# hall.net
KiCad netlist of a schematic drawn in Altium Designer
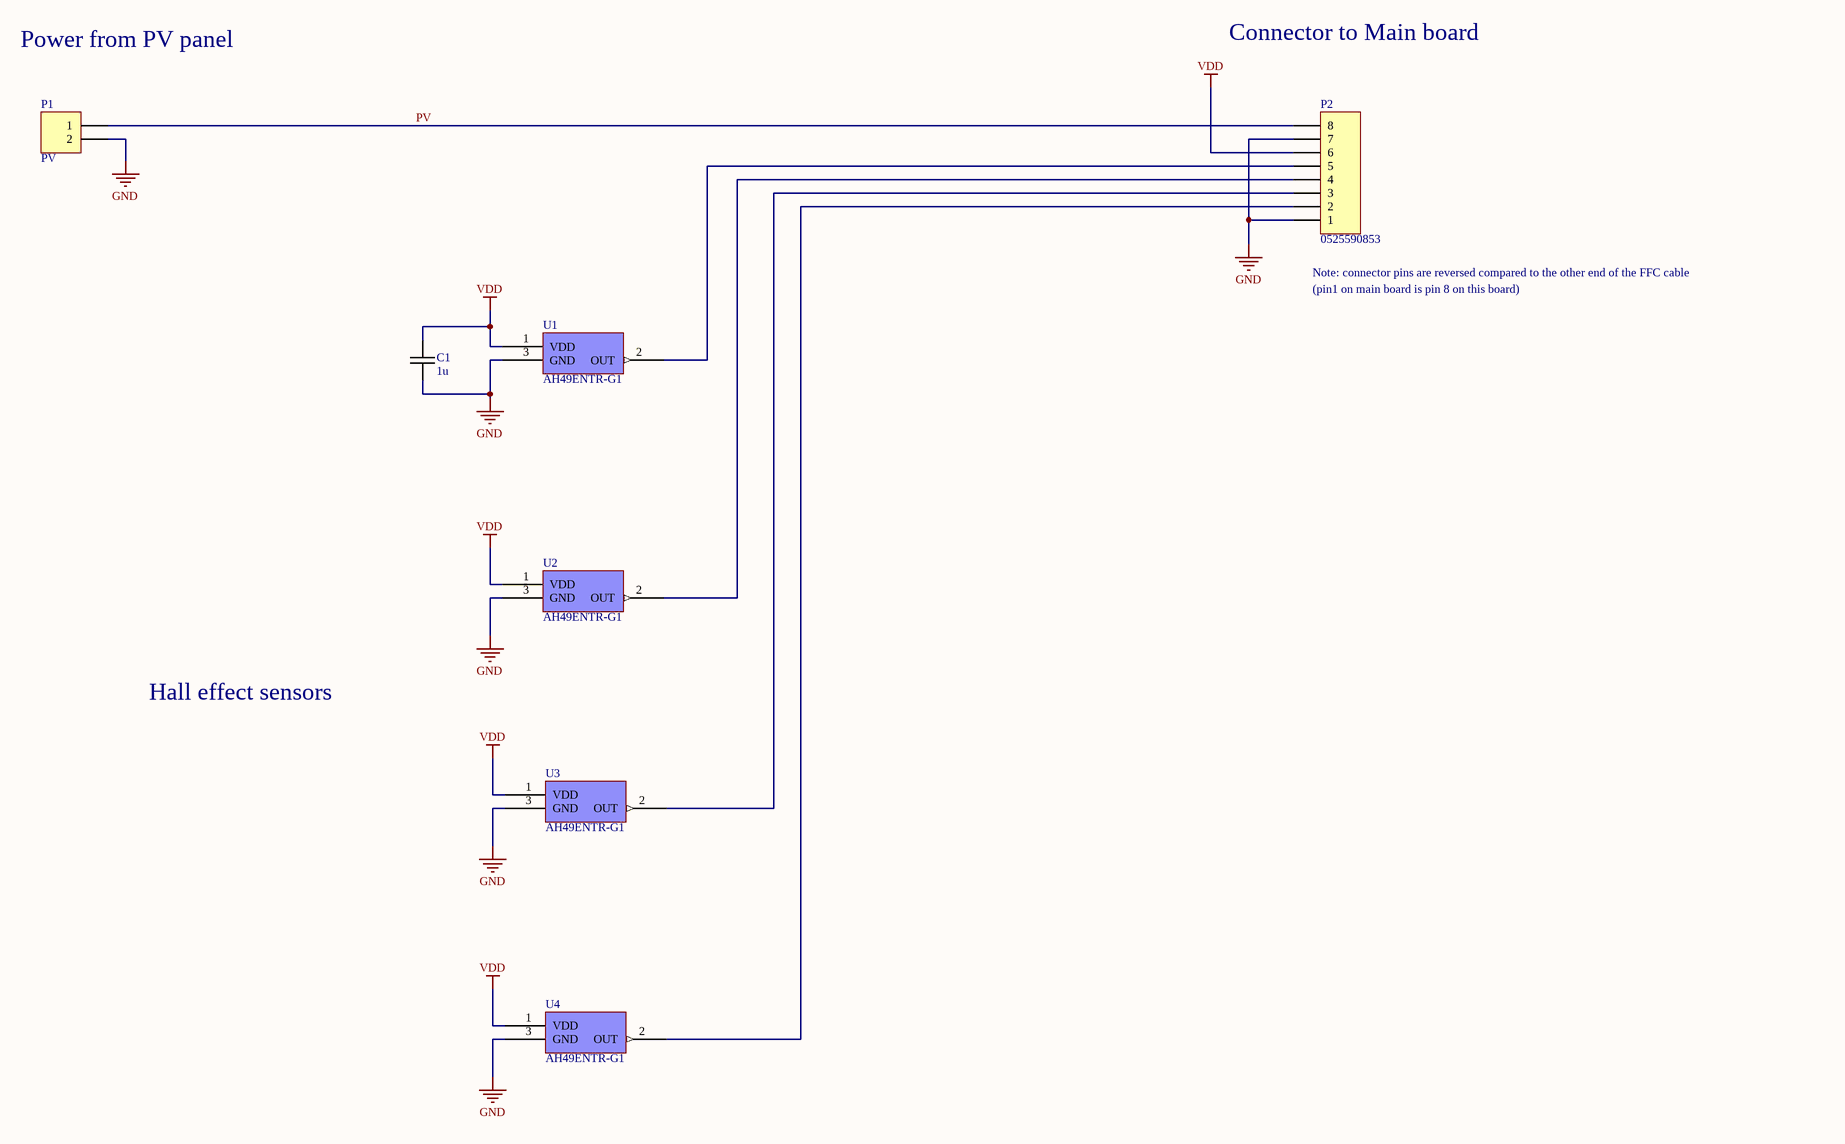
[diagram p0: hall.SchDoc]

(export (version "E")
  (design (tool "Eeschema 10.0.6"))
  (components
    (comp (ref "C1")
      (value "1u")
      (footprint "0805C-TBD")
      (description "CAPACITOR 0805 CERAMIC VALUE TO BE DETERMINED")
      (libsource (lib "vh_altium_library") (part "0805C-TBD"))
    )
    (comp (ref "P1")
      (value "PV")
      (footprint "HEADER-1X2")
      (description "Header, 2-Pin")
      (fields (field (name "PUBLISHER") "Altium Limited"))
      (libsource (lib "Miscellaneous Connectors") (part "Header 2"))
    )
    (comp (ref "P2")
      (value "0525590853")
      (footprint "FFC_8")
      (description "Header, 8-Pin")
      (fields (field (name "PUBLISHER") "Altium Limited"))
      (libsource (lib "Miscellaneous Connectors") (part "Header 8"))
    )
    (comp (ref "U1")
      (value "AH49ENTR-G1")
      (footprint "SOT23_AH49E")
      (description "Hall effect analog sensor")
      (libsource (lib "laf") (part "SI7211-B-00"))
    )
    (comp (ref "U2")
      (value "AH49ENTR-G1")
      (footprint "SOT23_AH49E")
      (description "Hall effect analog sensor")
      (libsource (lib "laf") (part "SI7211-B-00"))
    )
    (comp (ref "U3")
      (value "AH49ENTR-G1")
      (footprint "SOT23_AH49E")
      (description "Hall effect analog sensor")
      (libsource (lib "laf") (part "SI7211-B-00"))
    )
    (comp (ref "U4")
      (value "AH49ENTR-G1")
      (footprint "SOT23_AH49E")
      (description "Hall effect analog sensor")
      (libsource (lib "laf") (part "SI7211-B-00"))
    )
  )
  (nets
    (net (code "1") (name "/PV") (class "Default")
      (node (ref "P1") (pin "1") (pinfunction "1_1") (pintype "passive"))
      (node (ref "P2") (pin "8") (pinfunction "8_8") (pintype "passive"))
    )
    (net (code "2") (name "GND") (class "Default")
      (node (ref "C1") (pin "2") (pintype "passive"))
      (node (ref "P1") (pin "2") (pinfunction "2_2") (pintype "passive"))
      (node (ref "P2") (pin "1") (pinfunction "1_1") (pintype "passive"))
      (node (ref "P2") (pin "7") (pinfunction "7_7") (pintype "passive"))
      (node (ref "U1") (pin "3") (pinfunction "GND_3") (pintype "power_in"))
      (node (ref "U2") (pin "3") (pinfunction "GND_3") (pintype "power_in"))
      (node (ref "U3") (pin "3") (pinfunction "GND_3") (pintype "power_in"))
      (node (ref "U4") (pin "3") (pinfunction "GND_3") (pintype "power_in"))
    )
    (net (code "3") (name "Net-(U1-OUT)") (class "Default")
      (node (ref "P2") (pin "5") (pinfunction "5_5") (pintype "passive"))
      (node (ref "U1") (pin "2") (pinfunction "OUT_2") (pintype "output"))
    )
    (net (code "4") (name "Net-(U2-OUT)") (class "Default")
      (node (ref "P2") (pin "4") (pinfunction "4_4") (pintype "passive"))
      (node (ref "U2") (pin "2") (pinfunction "OUT_2") (pintype "output"))
    )
    (net (code "5") (name "Net-(U3-OUT)") (class "Default")
      (node (ref "P2") (pin "3") (pinfunction "3_3") (pintype "passive"))
      (node (ref "U3") (pin "2") (pinfunction "OUT_2") (pintype "output"))
    )
    (net (code "6") (name "Net-(U4-OUT)") (class "Default")
      (node (ref "P2") (pin "2") (pinfunction "2_2") (pintype "passive"))
      (node (ref "U4") (pin "2") (pinfunction "OUT_2") (pintype "output"))
    )
    (net (code "7") (name "VDD") (class "Default")
      (node (ref "C1") (pin "1") (pintype "passive"))
      (node (ref "P2") (pin "6") (pinfunction "6_6") (pintype "passive"))
      (node (ref "U1") (pin "1") (pinfunction "VDD_1") (pintype "power_in"))
      (node (ref "U2") (pin "1") (pinfunction "VDD_1") (pintype "power_in"))
      (node (ref "U3") (pin "1") (pinfunction "VDD_1") (pintype "power_in"))
      (node (ref "U4") (pin "1") (pinfunction "VDD_1") (pintype "power_in"))
    )
  )
)
